# rtu01n02.net
KiCad netlist of a schematic drawn in EAGLE
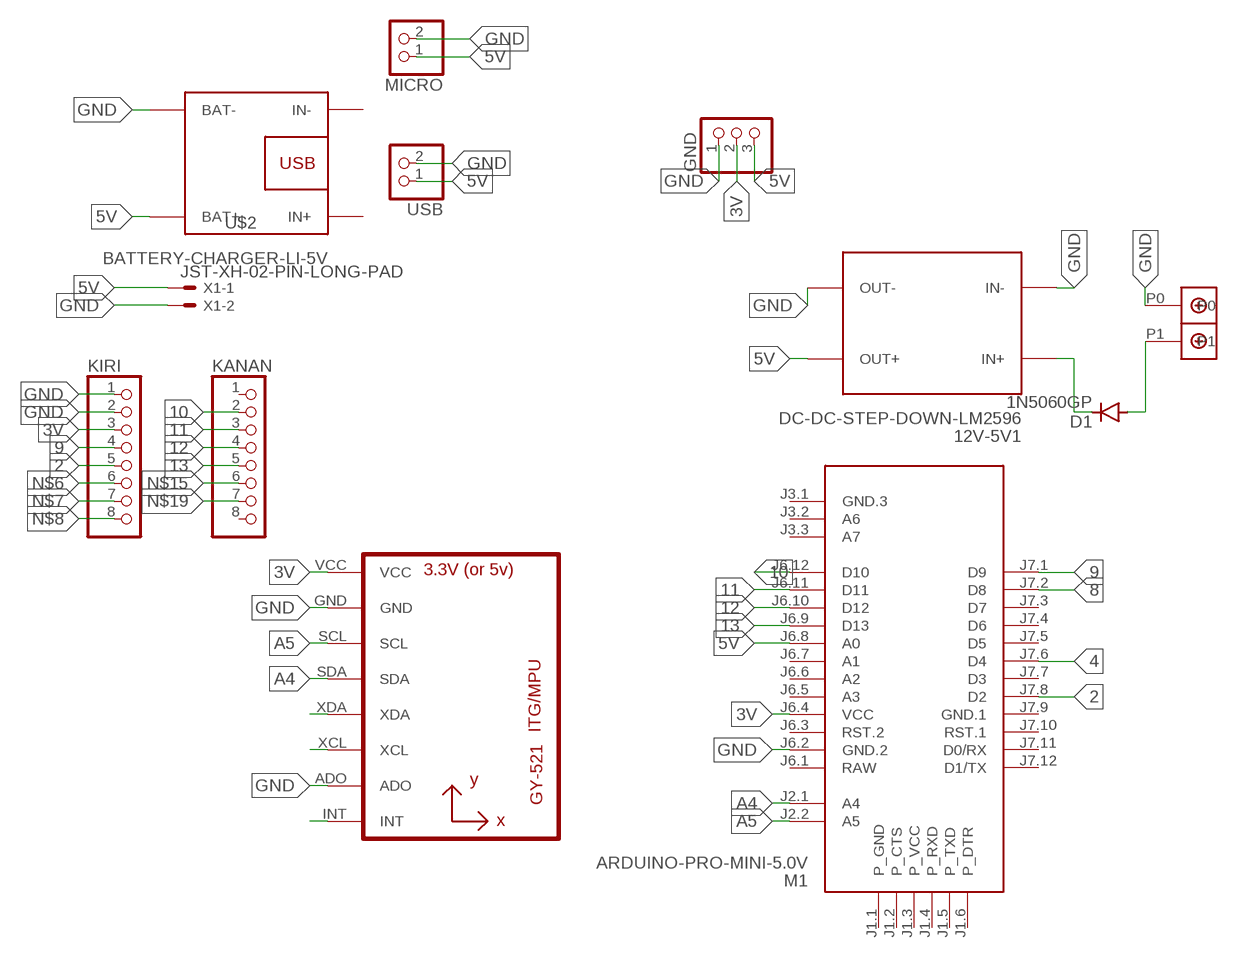
[diagram p0: schematic, sheet 1]

(export (version "E")
  (design (tool "Eeschema 10.0.6"))
  (components
    (comp (ref "12V-5V1")
      (value "DC-DC-STEP-DOWN-LM2596")
      (footprint "eagle-import:DC-DC-STEP-DOWN-LM2596")
      (libsource (lib "eagle-import") (part "DC-DC-STEP-DOWN-LM2596"))
    )
    (comp (ref "D1")
      (value "1N5060GP")
      (footprint "eagle-import:DO15-12")
      (libsource (lib "eagle-import") (part "1N5060GP"))
    )
    (comp (ref "GND")
      (value "PINHD-1X3")
      (footprint "eagle-import:1X03")
      (libsource (lib "eagle-import") (part "PINHD-1X3"))
    )
    (comp (ref "KANAN")
      (value "PINHD-1X8")
      (footprint "eagle-import:1X08")
      (libsource (lib "eagle-import") (part "PINHD-1X8"))
    )
    (comp (ref "KIRI")
      (value "PINHD-1X8")
      (footprint "eagle-import:1X08")
      (libsource (lib "eagle-import") (part "PINHD-1X8"))
    )
    (comp (ref "M1")
      (value "ARDUINO-PRO-MINI-5.0V")
      (footprint "eagle-import:ARDUINO-PRO-MINI")
      (libsource (lib "eagle-import") (part "ARDUINO-PRO-MINI-5.0V"))
    )
    (comp (ref "MICRO")
      (value "PINHD-1X2")
      (footprint "eagle-import:1X02")
      (libsource (lib "eagle-import") (part "PINHD-1X2"))
    )
    (comp (ref "U$1")
      (value "DBCONN-1X2")
      (footprint "eagle-import:DBCONN-1X2")
      (libsource (lib "eagle-import") (part "DBCONN-1X2"))
    )
    (comp (ref "U$2")
      (value "BATTERY-CHARGER-LI-5V")
      (footprint "eagle-import:BATTERY-CHARGER-LI-5V")
      (libsource (lib "eagle-import") (part "BATTERY-CHARGER-LI-5V"))
    )
    (comp (ref "U1")
      (value "GY-521MPU6050")
      (footprint "eagle-import:GY-521")
      (libsource (lib "eagle-import") (part "GY-521MPU6050"))
    )
    (comp (ref "USB")
      (value "PINHD-1X2")
      (footprint "eagle-import:1X02")
      (libsource (lib "eagle-import") (part "PINHD-1X2"))
    )
    (comp (ref "X1")
      (value "JST-XH-02-PIN-LONG-PAD")
      (footprint "eagle-import:JST-XH-02-PACKAGE-LONG-PAD")
      (libsource (lib "eagle-import") (part "JST-XH-02-PIN-LONG-PAD"))
    )
  )
  (nets
    (net (code "1") (name "/GND.1") (class "Default")
      (node (ref "M1") (pin "J7.9") (pinfunction "GND.1_J7.9") (pintype "power_in"))
    )
    (net (code "2") (name "/RAW") (class "Default")
      (node (ref "M1") (pin "J6.1") (pinfunction "RAW_J6.1") (pintype "power_in"))
    )
    (net (code "3") (name "2") (class "Default")
      (node (ref "KIRI") (pin "5") (pinfunction "5_5") (pintype "passive"))
      (node (ref "M1") (pin "J7.8") (pinfunction "D2_J7.8") (pintype "bidirectional"))
    )
    (net (code "4") (name "3V") (class "Default")
      (node (ref "GND") (pin "2") (pinfunction "2_2") (pintype "passive"))
      (node (ref "KIRI") (pin "3") (pinfunction "3_3") (pintype "passive"))
      (node (ref "M1") (pin "J6.4") (pinfunction "VCC_J6.4") (pintype "power_in"))
      (node (ref "U1") (pin "VCC") (pinfunction "VCC_VCC") (pintype "bidirectional"))
    )
    (net (code "5") (name "4") (class "Default")
      (node (ref "M1") (pin "J7.6") (pinfunction "D4_J7.6") (pintype "bidirectional"))
    )
    (net (code "6") (name "5V") (class "Default")
      (node (ref "12V-5V1") (pin "OUT+") (pinfunction "OUT+_OUT+") (pintype "bidirectional"))
      (node (ref "GND") (pin "3") (pinfunction "3_3") (pintype "passive"))
      (node (ref "M1") (pin "J6.8") (pinfunction "A0_J6.8") (pintype "bidirectional"))
      (node (ref "MICRO") (pin "1") (pinfunction "1_1") (pintype "passive"))
      (node (ref "U$2") (pin "BAT+") (pinfunction "BAT+_BAT+") (pintype "bidirectional"))
      (node (ref "USB") (pin "1") (pinfunction "1_1") (pintype "passive"))
      (node (ref "X1") (pin "1") (pinfunction "S_1") (pintype "passive"))
    )
    (net (code "7") (name "8") (class "Default")
      (node (ref "M1") (pin "J7.2") (pinfunction "D8_J7.2") (pintype "bidirectional"))
    )
    (net (code "8") (name "9") (class "Default")
      (node (ref "KIRI") (pin "4") (pinfunction "4_4") (pintype "passive"))
      (node (ref "M1") (pin "J7.1") (pinfunction "D9_J7.1") (pintype "bidirectional"))
    )
    (net (code "9") (name "10") (class "Default")
      (node (ref "KANAN") (pin "2") (pinfunction "2_2") (pintype "passive"))
      (node (ref "M1") (pin "J6.12") (pinfunction "D10_J6.12") (pintype "bidirectional"))
    )
    (net (code "10") (name "11") (class "Default")
      (node (ref "KANAN") (pin "3") (pinfunction "3_3") (pintype "passive"))
      (node (ref "M1") (pin "J6.11") (pinfunction "D11_J6.11") (pintype "bidirectional"))
    )
    (net (code "11") (name "12") (class "Default")
      (node (ref "KANAN") (pin "4") (pinfunction "4_4") (pintype "passive"))
      (node (ref "M1") (pin "J6.10") (pinfunction "D12_J6.10") (pintype "bidirectional"))
    )
    (net (code "12") (name "13") (class "Default")
      (node (ref "KANAN") (pin "5") (pinfunction "5_5") (pintype "passive"))
      (node (ref "M1") (pin "J6.9") (pinfunction "D13_J6.9") (pintype "bidirectional"))
    )
    (net (code "13") (name "A4") (class "Default")
      (node (ref "M1") (pin "J2.1") (pinfunction "A4_J2.1") (pintype "bidirectional"))
      (node (ref "U1") (pin "SDA") (pinfunction "SDA_SDA") (pintype "bidirectional"))
    )
    (net (code "14") (name "A5") (class "Default")
      (node (ref "M1") (pin "J2.2") (pinfunction "A5_J2.2") (pintype "bidirectional"))
      (node (ref "U1") (pin "SCL") (pinfunction "SCL_SCL") (pintype "bidirectional"))
    )
    (net (code "15") (name "GND") (class "Default")
      (node (ref "12V-5V1") (pin "IN-") (pinfunction "IN-_IN-") (pintype "bidirectional"))
      (node (ref "12V-5V1") (pin "OUT-") (pinfunction "OUT-_OUT-") (pintype "bidirectional"))
      (node (ref "GND") (pin "1") (pinfunction "1_1") (pintype "passive"))
      (node (ref "KIRI") (pin "1") (pinfunction "1_1") (pintype "passive"))
      (node (ref "KIRI") (pin "2") (pinfunction "2_2") (pintype "passive"))
      (node (ref "M1") (pin "J6.2") (pinfunction "GND.2_J6.2") (pintype "power_in"))
      (node (ref "MICRO") (pin "2") (pinfunction "2_2") (pintype "passive"))
      (node (ref "U$1") (pin "P0") (pinfunction "P0_P0") (pintype "bidirectional"))
      (node (ref "U$2") (pin "BAT-") (pinfunction "BAT-_BAT-") (pintype "bidirectional"))
      (node (ref "U1") (pin "ADO") (pinfunction "ADO_ADO") (pintype "bidirectional"))
      (node (ref "U1") (pin "GND") (pinfunction "GND_GND") (pintype "bidirectional"))
      (node (ref "USB") (pin "2") (pinfunction "2_2") (pintype "passive"))
      (node (ref "X1") (pin "2") (pinfunction "S_2") (pintype "passive"))
    )
    (net (code "16") (name "N$6") (class "Default")
      (node (ref "KIRI") (pin "6") (pinfunction "6_6") (pintype "passive"))
    )
    (net (code "17") (name "N$7") (class "Default")
      (node (ref "KIRI") (pin "7") (pinfunction "7_7") (pintype "passive"))
    )
    (net (code "18") (name "N$8") (class "Default")
      (node (ref "KIRI") (pin "8") (pinfunction "8_8") (pintype "passive"))
    )
    (net (code "19") (name "N$15") (class "Default")
      (node (ref "KANAN") (pin "6") (pinfunction "6_6") (pintype "passive"))
    )
    (net (code "20") (name "N$19") (class "Default")
      (node (ref "KANAN") (pin "7") (pinfunction "7_7") (pintype "passive"))
    )
    (net (code "21") (name "Net-(12V-5V1-PadIN+)") (class "Default")
      (node (ref "12V-5V1") (pin "IN+") (pinfunction "IN+_IN+") (pintype "bidirectional"))
      (node (ref "D1") (pin "C") (pinfunction "C_C") (pintype "passive"))
    )
    (net (code "22") (name "Net-(D1-PadA)") (class "Default")
      (node (ref "D1") (pin "A") (pinfunction "A_A") (pintype "passive"))
      (node (ref "U$1") (pin "P1") (pinfunction "P1_P1") (pintype "bidirectional"))
    )
    (net (code "23") (name "unconnected-(KANAN-Pad1)") (class "Default")
      (node (ref "KANAN") (pin "1") (pinfunction "1_1") (pintype "passive"))
    )
    (net (code "24") (name "unconnected-(KANAN-Pad8)") (class "Default")
      (node (ref "KANAN") (pin "8") (pinfunction "8_8") (pintype "passive"))
    )
    (net (code "25") (name "unconnected-(M1-A1-PadJ6.7)") (class "Default")
      (node (ref "M1") (pin "J6.7") (pinfunction "A1_J6.7") (pintype "bidirectional"))
    )
    (net (code "26") (name "unconnected-(M1-A2-PadJ6.6)") (class "Default")
      (node (ref "M1") (pin "J6.6") (pinfunction "A2_J6.6") (pintype "bidirectional"))
    )
    (net (code "27") (name "unconnected-(M1-A3-PadJ6.5)") (class "Default")
      (node (ref "M1") (pin "J6.5") (pinfunction "A3_J6.5") (pintype "bidirectional"))
    )
    (net (code "28") (name "unconnected-(M1-A6-PadJ3.2)") (class "Default")
      (node (ref "M1") (pin "J3.2") (pinfunction "A6_J3.2") (pintype "bidirectional"))
    )
    (net (code "29") (name "unconnected-(M1-A7-PadJ3.3)") (class "Default")
      (node (ref "M1") (pin "J3.3") (pinfunction "A7_J3.3") (pintype "bidirectional"))
    )
    (net (code "30") (name "unconnected-(M1-D0{slash}RX-PadJ7.11)") (class "Default")
      (node (ref "M1") (pin "J7.11") (pinfunction "D0/RX_J7.11") (pintype "bidirectional"))
    )
    (net (code "31") (name "unconnected-(M1-D1{slash}TX-PadJ7.12)") (class "Default")
      (node (ref "M1") (pin "J7.12") (pinfunction "D1/TX_J7.12") (pintype "bidirectional"))
    )
    (net (code "32") (name "unconnected-(M1-D3-PadJ7.7)") (class "Default")
      (node (ref "M1") (pin "J7.7") (pinfunction "D3_J7.7") (pintype "bidirectional"))
    )
    (net (code "33") (name "unconnected-(M1-D5-PadJ7.5)") (class "Default")
      (node (ref "M1") (pin "J7.5") (pinfunction "D5_J7.5") (pintype "bidirectional"))
    )
    (net (code "34") (name "unconnected-(M1-D6-PadJ7.4)") (class "Default")
      (node (ref "M1") (pin "J7.4") (pinfunction "D6_J7.4") (pintype "bidirectional"))
    )
    (net (code "35") (name "unconnected-(M1-D7-PadJ7.3)") (class "Default")
      (node (ref "M1") (pin "J7.3") (pinfunction "D7_J7.3") (pintype "bidirectional"))
    )
    (net (code "36") (name "unconnected-(M1-GND.3-PadJ3.1)") (class "Default")
      (node (ref "M1") (pin "J3.1") (pinfunction "GND.3_J3.1") (pintype "bidirectional"))
    )
    (net (code "37") (name "unconnected-(M1-P_CTS-PadJ1.2)") (class "Default")
      (node (ref "M1") (pin "J1.2") (pinfunction "P_CTS_J1.2") (pintype "bidirectional"))
    )
    (net (code "38") (name "unconnected-(M1-P_DTR-PadJ1.6)") (class "Default")
      (node (ref "M1") (pin "J1.6") (pinfunction "P_DTR_J1.6") (pintype "bidirectional"))
    )
    (net (code "39") (name "unconnected-(M1-P_GND-PadJ1.1)") (class "Default")
      (node (ref "M1") (pin "J1.1") (pinfunction "P_GND_J1.1") (pintype "bidirectional"))
    )
    (net (code "40") (name "unconnected-(M1-P_RXD-PadJ1.4)") (class "Default")
      (node (ref "M1") (pin "J1.4") (pinfunction "P_RXD_J1.4") (pintype "bidirectional"))
    )
    (net (code "41") (name "unconnected-(M1-P_TXD-PadJ1.5)") (class "Default")
      (node (ref "M1") (pin "J1.5") (pinfunction "P_TXD_J1.5") (pintype "bidirectional"))
    )
    (net (code "42") (name "unconnected-(M1-P_VCC-PadJ1.3)") (class "Default")
      (node (ref "M1") (pin "J1.3") (pinfunction "P_VCC_J1.3") (pintype "bidirectional"))
    )
    (net (code "43") (name "unconnected-(M1-RST.1-PadJ7.10)") (class "Default")
      (node (ref "M1") (pin "J7.10") (pinfunction "RST.1_J7.10") (pintype "bidirectional"))
    )
    (net (code "44") (name "unconnected-(M1-RST.2-PadJ6.3)") (class "Default")
      (node (ref "M1") (pin "J6.3") (pinfunction "RST.2_J6.3") (pintype "bidirectional"))
    )
    (net (code "45") (name "unconnected-(U$2-PadIN+)") (class "Default")
      (node (ref "U$2") (pin "IN+") (pinfunction "IN+_IN+") (pintype "bidirectional"))
    )
    (net (code "46") (name "unconnected-(U$2-PadIN-)") (class "Default")
      (node (ref "U$2") (pin "IN-") (pinfunction "IN-_IN-") (pintype "bidirectional"))
    )
    (net (code "47") (name "unconnected-(U1-PadINT)") (class "Default")
      (node (ref "U1") (pin "INT") (pinfunction "INT_INT") (pintype "bidirectional"))
    )
    (net (code "48") (name "unconnected-(U1-PadXCL)") (class "Default")
      (node (ref "U1") (pin "XCL") (pinfunction "XCL_XCL") (pintype "bidirectional"))
    )
    (net (code "49") (name "unconnected-(U1-PadXDA)") (class "Default")
      (node (ref "U1") (pin "XDA") (pinfunction "XDA_XDA") (pintype "bidirectional"))
    )
  )
)
